# JBCBJ.net
KiCad netlist of a schematic drawn in Altium Designer
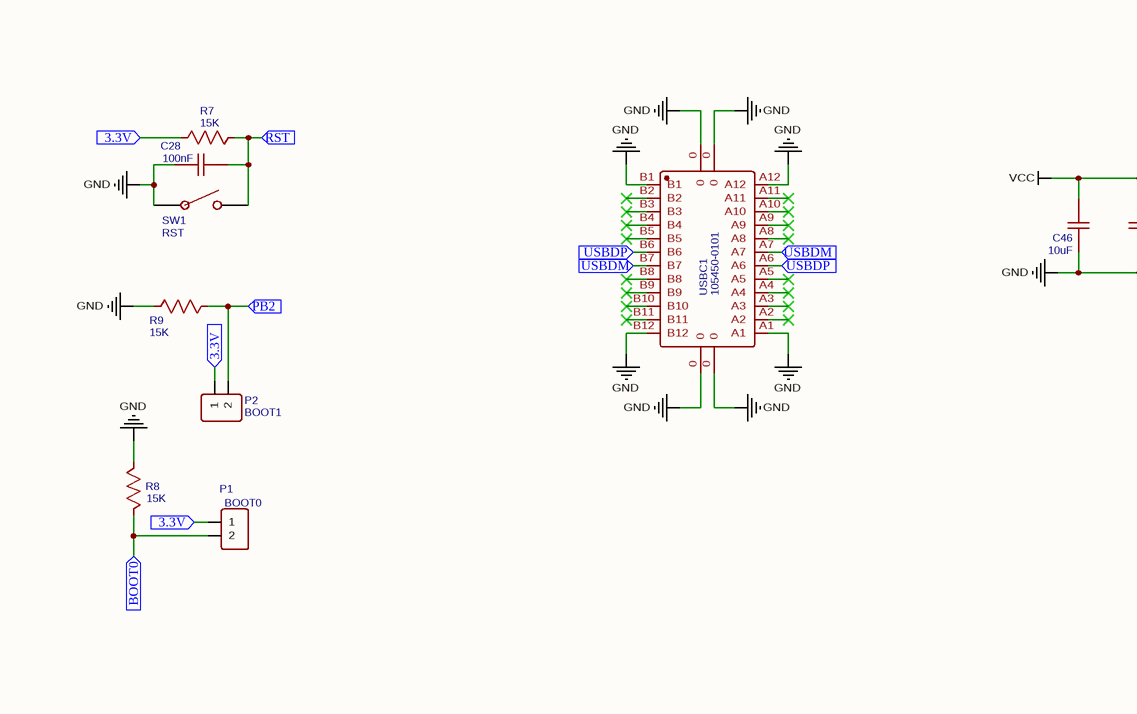
[diagram p0: JBCBJ.schdoc, top left]
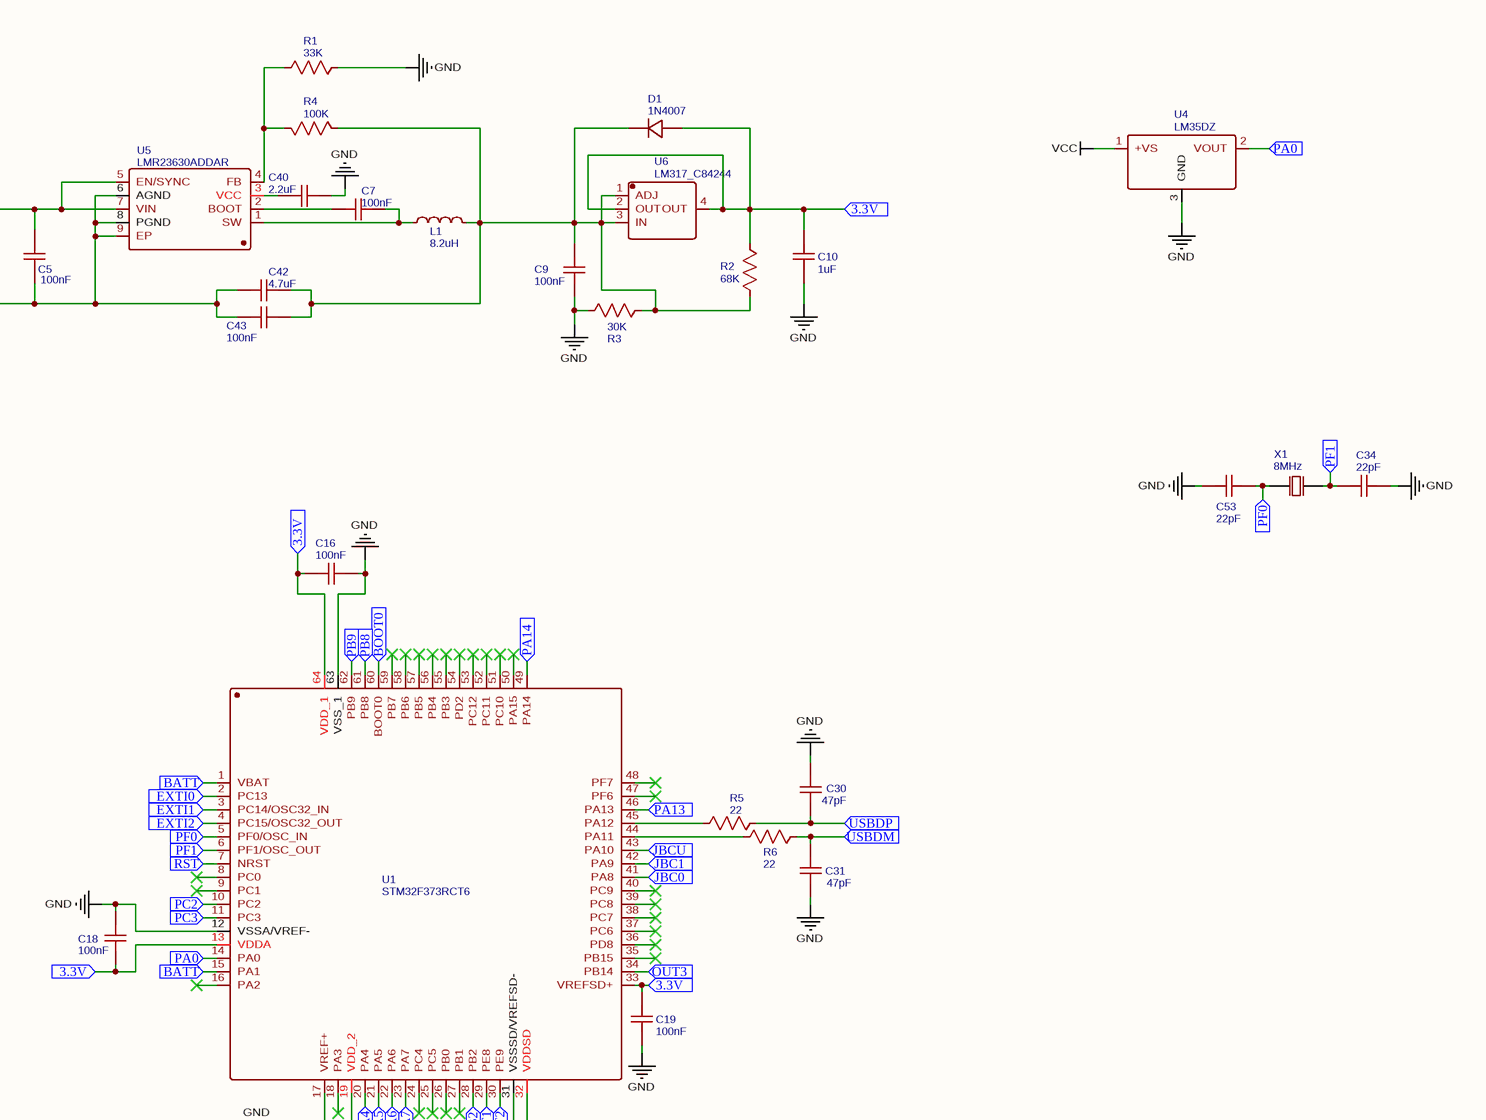
[diagram p1: JBCBJ.schdoc, top right]
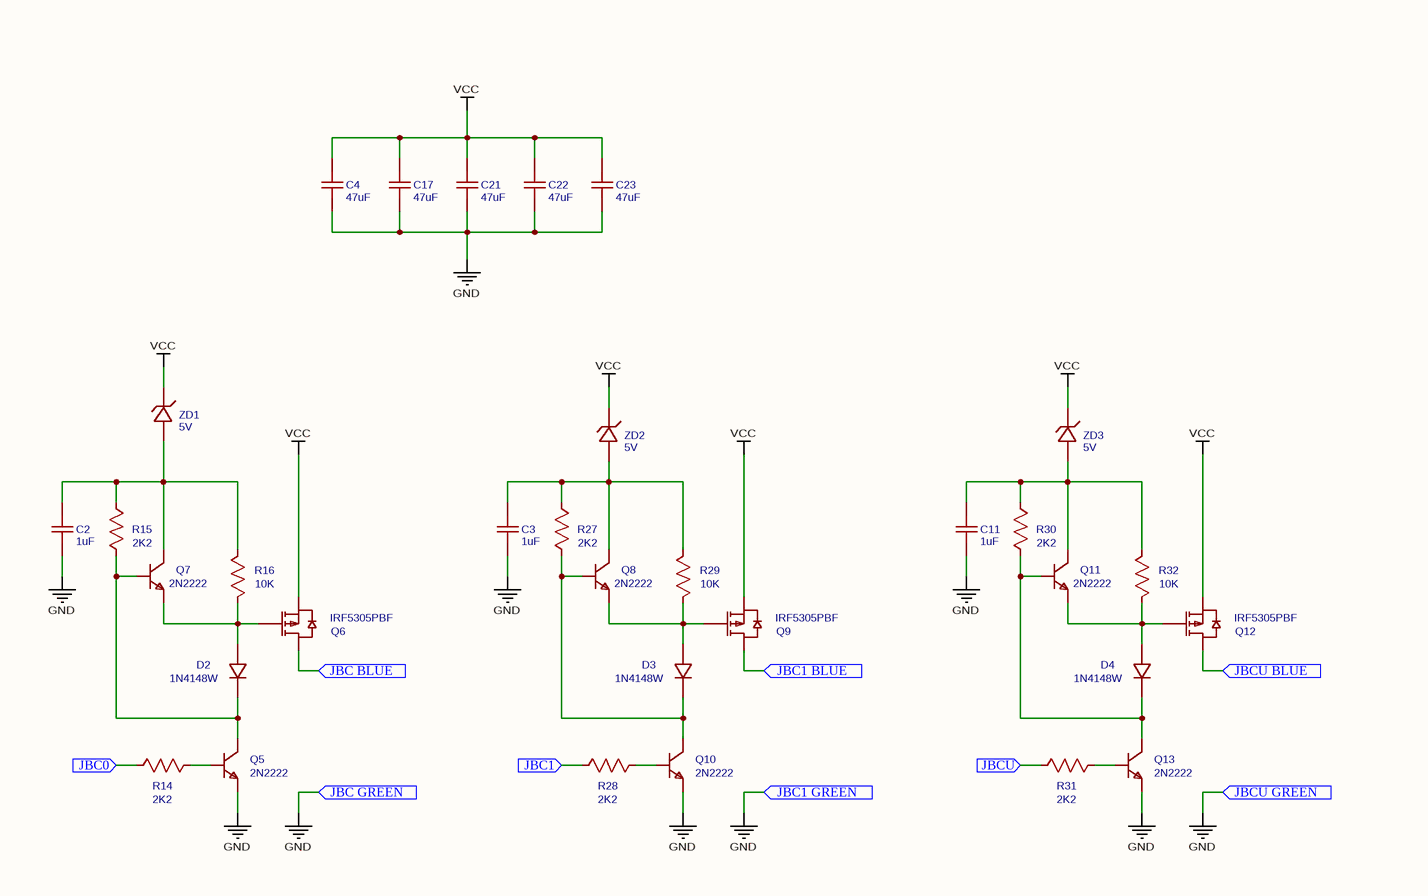
[diagram p2: JBCBJ.schdoc, bottom left]
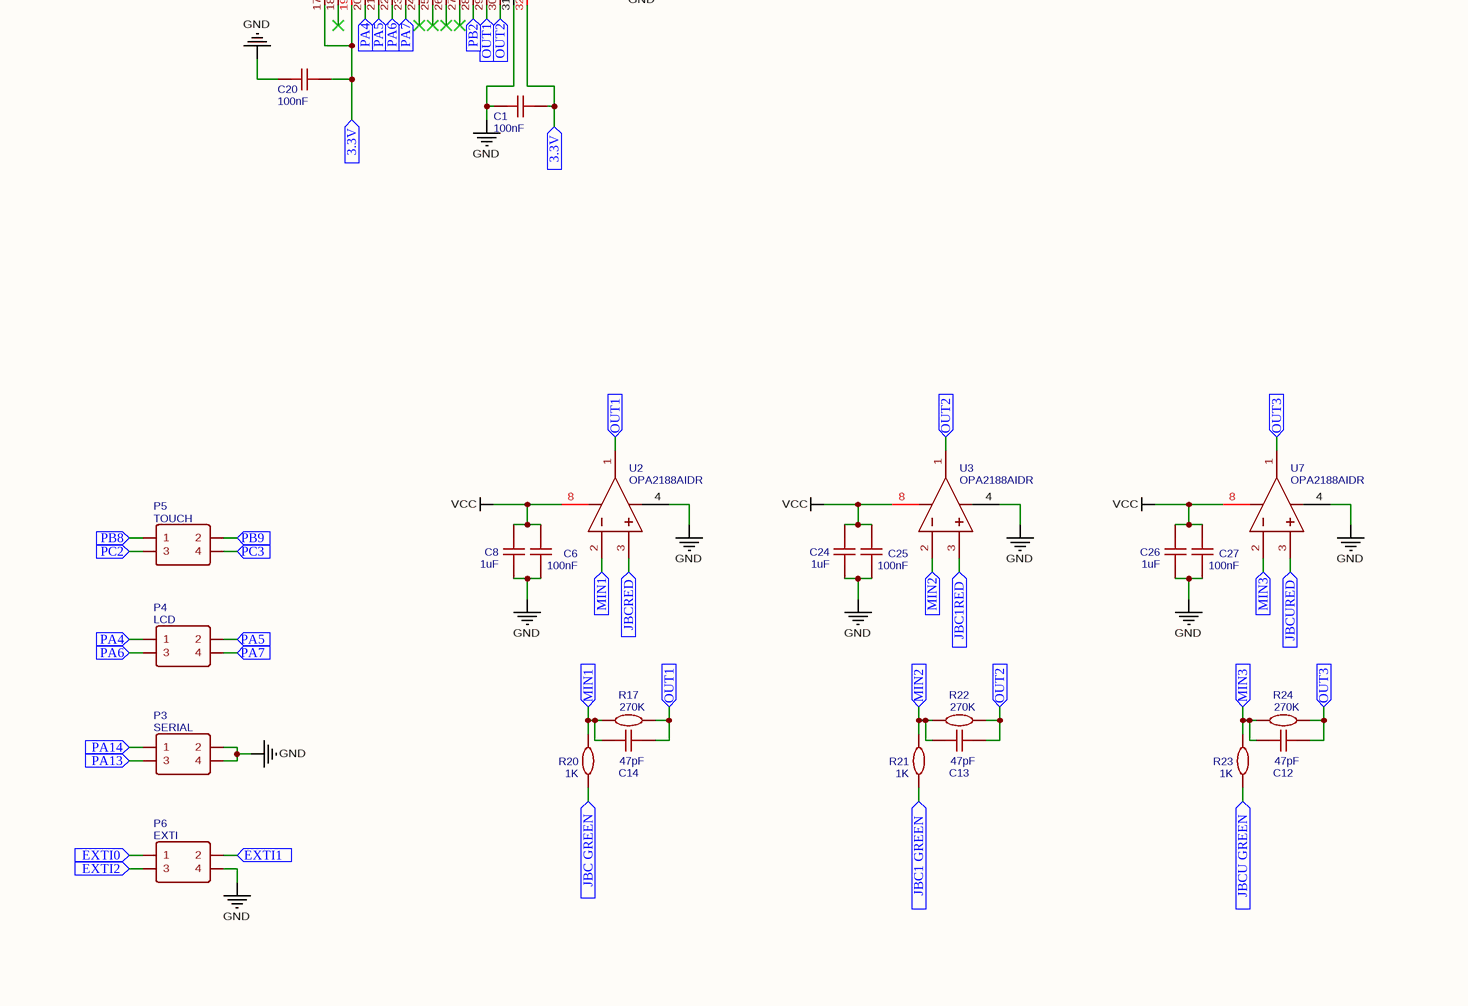
[diagram p3: JBCBJ.schdoc, bottom right]

(export (version "E")
  (design (tool "Eeschema 10.0.6"))
  (components
    (comp (ref "C1")
      (value "100nF")
      (footprint "C0603")
      (libsource (lib "altium-import") (part "root_1_100nF_"))
    )
    (comp (ref "C2")
      (value "1uF")
      (footprint "C0603")
      (fields (field (name "CONTRIBUTOR") "LCEDA_Lib"))
      (libsource (lib "altium-import") (part "root_1_1uF_"))
    )
    (comp (ref "C3")
      (value "1uF")
      (footprint "C0603")
      (fields (field (name "CONTRIBUTOR") "LCEDA_Lib"))
      (libsource (lib "altium-import") (part "root_1_1uF_"))
    )
    (comp (ref "C4")
      (value "47uF")
      (footprint "C1206")
      (fields (field (name "CONTRIBUTOR") "LCEDA_Lib"))
      (libsource (lib "altium-import") (part "root_1_47uF_"))
    )
    (comp (ref "C5") (value "100nF") (footprint "C0603") (libsource (lib "") (part "root_2_100nF__1")))
    (comp (ref "C6")
      (value "100nF")
      (footprint "C0603")
      (libsource (lib "altium-import") (part "root_2_100nF_"))
    )
    (comp (ref "C7")
      (value "100nF")
      (footprint "C0603")
      (libsource (lib "altium-import") (part "root_1_100nF_"))
    )
    (comp (ref "C8") (value "1uF") (footprint "C0603") (libsource (lib "altium-import") (part "root_2_1uF_")))
    (comp (ref "C9")
      (value "100nF")
      (footprint "C0603")
      (libsource (lib "altium-import") (part "root_0_100nF_"))
    )
    (comp (ref "C10")
      (value "1uF")
      (footprint "C0603")
      (libsource (lib "altium-import") (part "root_0_1uF_"))
    )
    (comp (ref "C11")
      (value "1uF")
      (footprint "C0603")
      (fields (field (name "CONTRIBUTOR") "LCEDA_Lib"))
      (libsource (lib "altium-import") (part "root_1_1uF_"))
    )
    (comp (ref "C12")
      (value "47pF")
      (footprint "C0603")
      (libsource (lib "altium-import") (part "root_3_47pF_"))
    )
    (comp (ref "C13")
      (value "47pF")
      (footprint "C0603")
      (libsource (lib "altium-import") (part "root_3_47pF_"))
    )
    (comp (ref "C14")
      (value "47pF")
      (footprint "C0603")
      (libsource (lib "altium-import") (part "root_3_47pF_"))
    )
    (comp (ref "C16")
      (value "100nF")
      (footprint "C0603")
      (libsource (lib "altium-import") (part "root_3_100nF_"))
    )
    (comp (ref "C17")
      (value "47uF")
      (footprint "C1206")
      (fields (field (name "CONTRIBUTOR") "LCEDA_Lib"))
      (libsource (lib "altium-import") (part "root_1_47uF_"))
    )
    (comp (ref "C18")
      (value "100nF")
      (footprint "C0603")
      (libsource (lib "altium-import") (part "root_0_100nF_"))
    )
    (comp (ref "C19")
      (value "100nF")
      (footprint "C0603")
      (libsource (lib "altium-import") (part "root_2_100nF_"))
    )
    (comp (ref "C20")
      (value "100nF")
      (footprint "C0603")
      (libsource (lib "altium-import") (part "root_1_100nF_"))
    )
    (comp (ref "C21")
      (value "47uF")
      (footprint "C1206")
      (fields (field (name "CONTRIBUTOR") "LCEDA_Lib"))
      (libsource (lib "altium-import") (part "root_1_47uF_"))
    )
    (comp (ref "C22")
      (value "47uF")
      (footprint "C1206")
      (fields (field (name "CONTRIBUTOR") "LCEDA_Lib"))
      (libsource (lib "altium-import") (part "root_1_47uF_"))
    )
    (comp (ref "C23")
      (value "47uF")
      (footprint "C1206")
      (fields (field (name "CONTRIBUTOR") "LCEDA_Lib"))
      (libsource (lib "altium-import") (part "root_1_47uF_"))
    )
    (comp (ref "C24")
      (value "1uF")
      (footprint "C0603")
      (libsource (lib "altium-import") (part "root_2_1uF_"))
    )
    (comp (ref "C25")
      (value "100nF")
      (footprint "C0603")
      (libsource (lib "altium-import") (part "root_2_100nF_"))
    )
    (comp (ref "C26")
      (value "1uF")
      (footprint "C0603")
      (libsource (lib "altium-import") (part "root_2_1uF_"))
    )
    (comp (ref "C27")
      (value "100nF")
      (footprint "C0603")
      (libsource (lib "altium-import") (part "root_2_100nF_"))
    )
    (comp (ref "C28") (value "100nF") (footprint "C0603") (libsource (lib "") (part "root_1_100nF__1")))
    (comp (ref "C30")
      (value "47pF")
      (footprint "C0603")
      (libsource (lib "altium-import") (part "root_2_47pF_"))
    )
    (comp (ref "C31")
      (value "47pF")
      (footprint "C0603")
      (libsource (lib "altium-import") (part "root_0_47pF_"))
    )
    (comp (ref "C34")
      (value "22pF")
      (footprint "C0603")
      (libsource (lib "altium-import") (part "root_3_22pF_"))
    )
    (comp (ref "C40")
      (value "2.2uF")
      (footprint "C0603")
      (libsource (lib "altium-import") (part "root_1_2.2uF_"))
    )
    (comp (ref "C42")
      (value "4.7uF")
      (footprint "C0603")
      (libsource (lib "altium-import") (part "root_1_4.7uF_"))
    )
    (comp (ref "C43")
      (value "100nF")
      (footprint "C0603")
      (libsource (lib "altium-import") (part "root_1_100nF_"))
    )
    (comp (ref "C46")
      (value "10uF")
      (footprint "C0603")
      (libsource (lib "altium-import") (part "root_2_10uF_"))
    )
    (comp (ref "C53")
      (value "22pF")
      (footprint "C0603")
      (libsource (lib "altium-import") (part "root_3_22pF_"))
    )
    (comp (ref "D1")
      (value "1N4007")
      (footprint "DO-214BA_L4.8-W2.9-LS5.3-RD")
      (fields (field (name "BOM_SUPPLIER PART") "C106903"))
      (libsource (lib "altium-import") (part "root_0_1N4007_"))
    )
    (comp (ref "D2")
      (value "1N4148W")
      (footprint "SOD-323F_L2.0-W1.6-LS2.5-RD")
      (fields (field (name "BOM_SUPPLIER PART") "C129216") (field (name "CONTRIBUTOR") "LCEDA_Lib"))
      (libsource (lib "altium-import") (part "root_3_1N4148W_"))
    )
    (comp (ref "D3")
      (value "1N4148W")
      (footprint "SOD-323F_L2.0-W1.6-LS2.5-RD")
      (fields (field (name "BOM_SUPPLIER PART") "C129216") (field (name "CONTRIBUTOR") "LCEDA_Lib"))
      (libsource (lib "altium-import") (part "root_3_1N4148W_"))
    )
    (comp (ref "D4")
      (value "1N4148W")
      (footprint "SOD-323F_L2.0-W1.6-LS2.5-RD")
      (fields (field (name "BOM_SUPPLIER PART") "C129216") (field (name "CONTRIBUTOR") "LCEDA_Lib"))
      (libsource (lib "altium-import") (part "root_3_1N4148W_"))
    )
    (comp (ref "L1")
      (value "8.2uH")
      (footprint "IND-SMD_L7.8-W7.0_MAPM0630F")
      (fields
        (field (name "BOM_SUPPLIER PART") "C280926")
        (field (name "BOM_MANUFACTURER PART") "MAPM0630F-8R2M-LF")
        (field (name "CONTRIBUTOR") "LCSC")
      )
      (libsource (lib "altium-import") (part "root_2_8.2uH_"))
    )
    (comp (ref "P1")
      (value "BOOT0")
      (footprint "HDR-TH_2P-P2.54-V-M")
      (fields
        (field (name "BOM_MANUFACTURER PART") "2.54-1*2PFemale")
        (field (name "BOM_SUPPLIER PART") "C49661")
      )
      (libsource (lib "altium-import") (part "root_0_BOOT0_"))
    )
    (comp (ref "P2")
      (value "BOOT1")
      (footprint "HDR-TH_2P-P2.54-V-M")
      (fields
        (field (name "BOM_MANUFACTURER PART") "2.54-1*2PFemale")
        (field (name "BOM_SUPPLIER PART") "C49661")
      )
      (libsource (lib "altium-import") (part "root_3_BOOT1_"))
    )
    (comp (ref "P3")
      (value "SERIAL")
      (footprint "HDR-TH_4PIN-V-ROW2-COL2-MALE-PITCH2.54")
      (fields
        (field (name "BOM_MANUFACTURER PART") "Double Rows2.54mm2*2pHeaders  Pins")
        (field (name "BOM_SUPPLIER PART") "C66690")
      )
      (libsource (lib "altium-import") (part "root_0_SERIAL_"))
    )
    (comp (ref "P4")
      (value "LCD")
      (footprint "HDR-TH_4PIN-V-ROW2-COL2-MALE-PITCH2.54")
      (fields
        (field (name "BOM_MANUFACTURER PART") "Double Rows2.54mm2*2pHeaders  Pins")
        (field (name "BOM_SUPPLIER PART") "C66690")
      )
      (libsource (lib "altium-import") (part "root_0_LCD_"))
    )
    (comp (ref "P5")
      (value "TOUCH")
      (footprint "HDR-TH_4PIN-V-ROW2-COL2-MALE-PITCH2.54")
      (fields
        (field (name "BOM_MANUFACTURER PART") "Double Rows2.54mm2*2pHeaders  Pins")
        (field (name "BOM_SUPPLIER PART") "C66690")
      )
      (libsource (lib "altium-import") (part "root_0_TOUCH_"))
    )
    (comp (ref "P6")
      (value "EXTI")
      (footprint "HDR-TH_4PIN-V-ROW2-COL2-MALE-PITCH2.54")
      (fields
        (field (name "BOM_MANUFACTURER PART") "Double Rows2.54mm2*2pHeaders  Pins")
        (field (name "BOM_SUPPLIER PART") "C66690")
      )
      (libsource (lib "altium-import") (part "root_0_EXTI_"))
    )
    (comp (ref "Q5")
      (value "2N2222")
      (footprint "SOT-23-3_L2.9-W1.3-P1.90-LS2.4-BR")
      (fields (field (name "BOM_MANUFACTURER PART") "2N3904") (field (name "BOM_SUPPLIER PART") "C118538"))
      (libsource (lib "altium-import") (part "root_0_2N2222_"))
    )
    (comp (ref "Q6")
      (value "IRF5305PBF")
      (footprint "DPAK-3_L6.6-W6.1-P2.28-LS9.9-BR")
      (fields (field (name "BOM_SUPPLIER PART") "C2623"))
      (libsource (lib "altium-import") (part "root_0_IRF5305PBF_"))
    )
    (comp (ref "Q7")
      (value "2N2222")
      (footprint "SOT-23-3_L2.9-W1.3-P1.90-LS2.4-BR")
      (fields (field (name "BOM_SUPPLIER PART") "C118536") (field (name "CONTRIBUTOR") "LCSC"))
      (libsource (lib "altium-import") (part "root_0_2N2222_"))
    )
    (comp (ref "Q8")
      (value "2N2222")
      (footprint "SOT-23-3_L2.9-W1.3-P1.90-LS2.4-BR")
      (fields (field (name "BOM_SUPPLIER PART") "C118536") (field (name "CONTRIBUTOR") "LCSC"))
      (libsource (lib "altium-import") (part "root_0_2N2222_"))
    )
    (comp (ref "Q9")
      (value "IRF5305PBF")
      (footprint "DPAK-3_L6.6-W6.1-P2.28-LS9.9-BR")
      (fields (field (name "BOM_SUPPLIER PART") "C2623"))
      (libsource (lib "altium-import") (part "root_0_IRF5305PBF_"))
    )
    (comp (ref "Q10")
      (value "2N2222")
      (footprint "SOT-23-3_L2.9-W1.3-P1.90-LS2.4-BR")
      (fields (field (name "BOM_MANUFACTURER PART") "2N3904") (field (name "BOM_SUPPLIER PART") "C118538"))
      (libsource (lib "altium-import") (part "root_0_2N2222_"))
    )
    (comp (ref "Q11")
      (value "2N2222")
      (footprint "SOT-23-3_L2.9-W1.3-P1.90-LS2.4-BR")
      (fields (field (name "BOM_SUPPLIER PART") "C118536") (field (name "CONTRIBUTOR") "LCSC"))
      (libsource (lib "altium-import") (part "root_0_2N2222_"))
    )
    (comp (ref "Q12")
      (value "IRF5305PBF")
      (footprint "DPAK-3_L6.6-W6.1-P2.28-LS9.9-BR")
      (fields (field (name "BOM_SUPPLIER PART") "C2623"))
      (libsource (lib "altium-import") (part "root_0_IRF5305PBF_"))
    )
    (comp (ref "Q13")
      (value "2N2222")
      (footprint "SOT-23-3_L2.9-W1.3-P1.90-LS2.4-BR")
      (fields (field (name "BOM_MANUFACTURER PART") "2N3904") (field (name "BOM_SUPPLIER PART") "C118538"))
      (libsource (lib "altium-import") (part "root_0_2N2222_"))
    )
    (comp (ref "R1") (value "33K") (footprint "R0603") (libsource (lib "altium-import") (part "root_2_33K_")))
    (comp (ref "R2") (value "68K") (footprint "R0603") (libsource (lib "altium-import") (part "root_1_68K_")))
    (comp (ref "R3") (value "30K") (footprint "R0603") (libsource (lib "altium-import") (part "root_2_30K_")))
    (comp (ref "R4")
      (value "100K")
      (footprint "R0603")
      (libsource (lib "altium-import") (part "root_0_100K_"))
    )
    (comp (ref "R5") (value "22") (footprint "R0603") (libsource (lib "altium-import") (part "root_0_22_")))
    (comp (ref "R6") (value "22") (footprint "R0603") (libsource (lib "altium-import") (part "root_0_22_")))
    (comp (ref "R7") (value "15K") (footprint "R0603") (libsource (lib "altium-import") (part "root_0_15K_")))
    (comp (ref "R8") (value "15K") (footprint "R0603") (libsource (lib "altium-import") (part "root_3_15K_")))
    (comp (ref "R9") (value "15K") (footprint "R0603") (libsource (lib "altium-import") (part "root_2_15K_")))
    (comp (ref "R14")
      (value "2K2")
      (footprint "R0603")
      (fields (field (name "CONTRIBUTOR") "LCEDA_Lib"))
      (libsource (lib "altium-import") (part "root_0_2K2_"))
    )
    (comp (ref "R15")
      (value "2K2")
      (footprint "R0603")
      (fields (field (name "CONTRIBUTOR") "LCEDA_Lib"))
      (libsource (lib "altium-import") (part "root_1_2K2_"))
    )
    (comp (ref "R16")
      (value "10K")
      (footprint "R0603")
      (libsource (lib "altium-import") (part "root_3_10K_"))
    )
    (comp (ref "R17")
      (value "270K")
      (footprint "R0603")
      (fields
        (field (name "BOM_SUPPLIER PART") "C351588")
        (field (name "BOM_MANUFACTURER PART") "PTFR0805B270KN9")
        (field (name "CONTRIBUTOR") "LCSC")
      )
      (libsource (lib "altium-import") (part "root_2_270K_"))
    )
    (comp (ref "R20")
      (value "1K")
      (footprint "R0603")
      (fields
        (field (name "BOM_SUPPLIER PART") "C192073")
        (field (name "BOM_MANUFACTURER PART") "ERA-6AEB102V")
        (field (name "CONTRIBUTOR") "LCSC")
      )
      (libsource (lib "altium-import") (part "root_1_1K_"))
    )
    (comp (ref "R21")
      (value "1K")
      (footprint "R0603")
      (fields
        (field (name "BOM_SUPPLIER PART") "C192073")
        (field (name "BOM_MANUFACTURER PART") "ERA-6AEB102V")
        (field (name "CONTRIBUTOR") "LCSC")
      )
      (libsource (lib "altium-import") (part "root_1_1K_"))
    )
    (comp (ref "R22")
      (value "270K")
      (footprint "R0603")
      (fields
        (field (name "BOM_SUPPLIER PART") "C351588")
        (field (name "BOM_MANUFACTURER PART") "PTFR0805B270KN9")
        (field (name "CONTRIBUTOR") "LCSC")
      )
      (libsource (lib "altium-import") (part "root_2_270K_"))
    )
    (comp (ref "R23")
      (value "1K")
      (footprint "R0603")
      (fields
        (field (name "BOM_SUPPLIER PART") "C192073")
        (field (name "BOM_MANUFACTURER PART") "ERA-6AEB102V")
        (field (name "CONTRIBUTOR") "LCSC")
      )
      (libsource (lib "altium-import") (part "root_1_1K_"))
    )
    (comp (ref "R24")
      (value "270K")
      (footprint "R0603")
      (fields
        (field (name "BOM_SUPPLIER PART") "C351588")
        (field (name "BOM_MANUFACTURER PART") "PTFR0805B270KN9")
        (field (name "CONTRIBUTOR") "LCSC")
      )
      (libsource (lib "altium-import") (part "root_2_270K_"))
    )
    (comp (ref "R27")
      (value "2K2")
      (footprint "R0603")
      (fields (field (name "CONTRIBUTOR") "LCEDA_Lib"))
      (libsource (lib "altium-import") (part "root_1_2K2_"))
    )
    (comp (ref "R28")
      (value "2K2")
      (footprint "R0603")
      (fields (field (name "CONTRIBUTOR") "LCEDA_Lib"))
      (libsource (lib "altium-import") (part "root_0_2K2_"))
    )
    (comp (ref "R29")
      (value "10K")
      (footprint "R0603")
      (libsource (lib "altium-import") (part "root_3_10K_"))
    )
    (comp (ref "R30")
      (value "2K2")
      (footprint "R0603")
      (fields (field (name "CONTRIBUTOR") "LCEDA_Lib"))
      (libsource (lib "altium-import") (part "root_1_2K2_"))
    )
    (comp (ref "R31")
      (value "2K2")
      (footprint "R0603")
      (fields (field (name "CONTRIBUTOR") "LCEDA_Lib"))
      (libsource (lib "altium-import") (part "root_0_2K2_"))
    )
    (comp (ref "R32")
      (value "10K")
      (footprint "R0603")
      (libsource (lib "altium-import") (part "root_3_10K_"))
    )
    (comp (ref "SW1")
      (value "RST")
      (footprint "KEY-6.0*6.0-4")
      (fields
        (field (name "BOM_MANUFACTURER PART") "EVQ22705R")
        (field (name "BOM_SUPPLIER PART") "C79156")
        (field (name "CONTRIBUTOR") "LCSC")
      )
      (libsource (lib "altium-import") (part "root_0_RST_"))
    )
    (comp (ref "U1")
      (value "STM32F373RCT6")
      (footprint "LQFP-64_L10.0-W10.0-P0.50-LS12.0-TL")
      (fields (field (name "BOM_SUPPLIER PART") "C84174"))
      (libsource (lib "altium-import") (part "root_0_STM32F373RCT6_"))
    )
    (comp (ref "U2")
      (value "OPA2188AIDR")
      (footprint "SOIC-8_L4.9-W3.9-P1.27-LS6.0-BL")
      (fields (field (name "BOM_SUPPLIER PART") "C17271") (field (name "SUBPART_NO") "1"))
      (libsource (lib "altium-import") (part "root_1_OPA2188AIDR_"))
    )
    (comp (ref "U3")
      (value "OPA2188AIDR")
      (footprint "SOIC-8_L4.9-W3.9-P1.27-LS6.0-BL")
      (fields (field (name "BOM_SUPPLIER PART") "C17271") (field (name "SUBPART_NO") "1"))
      (libsource (lib "altium-import") (part "root_1_OPA2188AIDR_"))
    )
    (comp (ref "U4")
      (value "LM35DZ")
      (footprint "TO-92-3_L4.9-W3.7-P1.27-L")
      (fields (field (name "BOM_SUPPLIER PART") "C12165"))
      (libsource (lib "altium-import") (part "root_0_LM35DZ_"))
    )
    (comp (ref "U5")
      (value "LMR23630ADDAR")
      (footprint "SO-8_L4.9-W3.9-P1.27-LS6.0-BL-EP")
      (fields (field (name "BOM_SUPPLIER PART") "C477923") (field (name "CONTRIBUTOR") "LCSC"))
      (libsource (lib "altium-import") (part "root_2_LMR23630ADDAR_"))
    )
    (comp (ref "U6")
      (value "LM317_C84244")
      (footprint "SOT-223-3_L6.5-W3.4-P2.30-LS7.0-BR")
      (fields (field (name "BOM_MANUFACTURER PART") "LM317") (field (name "BOM_SUPPLIER PART") "C84244"))
      (libsource (lib "altium-import") (part "root_0_LM317_C84244_"))
    )
    (comp (ref "U7")
      (value "OPA2188AIDR")
      (footprint "SOIC-8_L4.9-W3.9-P1.27-LS6.0-BL")
      (fields (field (name "BOM_SUPPLIER PART") "C17271") (field (name "SUBPART_NO") "1"))
      (libsource (lib "altium-import") (part "root_1_OPA2188AIDR_"))
    )
    (comp (ref "USBC1")
      (value "105450-0101")
      (footprint "USB-C-SMD_TYPE-C-USB-18")
      (fields (field (name "BOM_SUPPLIER PART") "C134092") (field (name "CONTRIBUTOR") "LCSC"))
      (libsource (lib "altium-import") (part "root_0_105450-0101_"))
    )
    (comp (ref "X1")
      (value "8MHz")
      (footprint "HC-49US_L11.5-W4.5-P4.88")
      (fields
        (field (name "BOM_SUPPLIER PART") "C188205")
        (field (name "BOM_MANUFACTURER PART") "X49SD8MSB2SI")
        (field (name "CONTRIBUTOR") "LCSC")
      )
      (libsource (lib "altium-import") (part "root_0_8MHz_"))
    )
    (comp (ref "ZD1")
      (value "5V")
      (footprint "VERTICAL DO41 DIODE")
      (fields (field (name "BOM_MANUFACTURER PART") "BZX84C5V1") (field (name "BOM_SUPPLIER PART") "C27131"))
      (libsource (lib "altium-import") (part "root_1_5V_"))
    )
    (comp (ref "ZD2")
      (value "5V")
      (footprint "VERTICAL DO41 DIODE")
      (fields (field (name "BOM_MANUFACTURER PART") "BZX84C5V1") (field (name "BOM_SUPPLIER PART") "C27131"))
      (libsource (lib "altium-import") (part "root_1_5V_"))
    )
    (comp (ref "ZD3")
      (value "5V")
      (footprint "VERTICAL DO41 DIODE")
      (fields (field (name "BOM_MANUFACTURER PART") "BZX84C5V1") (field (name "BOM_SUPPLIER PART") "C27131"))
      (libsource (lib "altium-import") (part "root_1_5V_"))
    )
  )
  (nets
    (net (code "1") (name "/3.3V") (class "Default")
      (node (ref "C1") (pin "1") (pinfunction "1_1") (pintype "passive"))
      (node (ref "C10") (pin "2") (pinfunction "2_2") (pintype "passive"))
      (node (ref "C16") (pin "1") (pinfunction "1_1") (pintype "passive"))
      (node (ref "C18") (pin "1") (pinfunction "1_1") (pintype "passive"))
      (node (ref "C19") (pin "1") (pinfunction "1_1") (pintype "passive"))
      (node (ref "C20") (pin "1") (pinfunction "1_1") (pintype "passive"))
      (node (ref "D1") (pin "2") (pinfunction "A_2") (pintype "passive"))
      (node (ref "P1") (pin "1") (pinfunction "1_1") (pintype "passive"))
      (node (ref "P2") (pin "1") (pinfunction "1_1") (pintype "passive"))
      (node (ref "R2") (pin "2") (pinfunction "2_2") (pintype "passive"))
      (node (ref "R7") (pin "1") (pinfunction "1_1") (pintype "passive"))
      (node (ref "U1") (pin "13") (pinfunction "VDDA_13") (pintype "passive"))
      (node (ref "U1") (pin "17") (pinfunction "VREF+_17") (pintype "passive"))
      (node (ref "U1") (pin "19") (pinfunction "VDD_2_19") (pintype "passive"))
      (node (ref "U1") (pin "32") (pinfunction "VDDSD_32") (pintype "passive"))
      (node (ref "U1") (pin "33") (pinfunction "VREFSD+_33") (pintype "passive"))
      (node (ref "U1") (pin "64") (pinfunction "VDD_1_64") (pintype "passive"))
      (node (ref "U6") (pin "2") (pinfunction "OUT_2") (pintype "passive"))
      (node (ref "U6") (pin "4") (pinfunction "OUT_4") (pintype "passive"))
    )
    (net (code "2") (name "/BATT") (class "Default")
      (node (ref "U1") (pin "1") (pinfunction "VBAT_1") (pintype "passive"))
      (node (ref "U1") (pin "15") (pinfunction "PA1_15") (pintype "passive"))
    )
    (net (code "3") (name "/BOOT0") (class "Default")
      (node (ref "P1") (pin "2") (pinfunction "2_2") (pintype "passive"))
      (node (ref "R8") (pin "1") (pinfunction "1_1") (pintype "passive"))
      (node (ref "U1") (pin "60") (pinfunction "BOOT0_60") (pintype "passive"))
    )
    (net (code "4") (name "/EXTI0") (class "Default")
      (node (ref "P6") (pin "1") (pinfunction "1_1") (pintype "passive"))
      (node (ref "U1") (pin "2") (pinfunction "PC13_2") (pintype "passive"))
    )
    (net (code "5") (name "/EXTI1") (class "Default")
      (node (ref "P6") (pin "2") (pinfunction "2_2") (pintype "passive"))
      (node (ref "U1") (pin "3") (pinfunction "PC14/OSC32_IN_3") (pintype "passive"))
    )
    (net (code "6") (name "/EXTI2") (class "Default")
      (node (ref "P6") (pin "3") (pinfunction "3_3") (pintype "passive"))
      (node (ref "U1") (pin "4") (pinfunction "PC15/OSC32_OUT_4") (pintype "passive"))
    )
    (net (code "7") (name "/JBC BLUE") (class "Default")
      (node (ref "Q6") (pin "2") (pinfunction "D_2") (pintype "passive"))
    )
    (net (code "8") (name "/JBC0") (class "Default")
      (node (ref "R14") (pin "1") (pinfunction "1_1") (pintype "passive"))
      (node (ref "U1") (pin "41") (pinfunction "PA8_41") (pintype "passive"))
    )
    (net (code "9") (name "/JBC1") (class "Default")
      (node (ref "R28") (pin "1") (pinfunction "1_1") (pintype "passive"))
      (node (ref "U1") (pin "42") (pinfunction "PA9_42") (pintype "passive"))
    )
    (net (code "10") (name "/JBC1 BLUE") (class "Default")
      (node (ref "Q9") (pin "2") (pinfunction "D_2") (pintype "passive"))
    )
    (net (code "11") (name "/JBC1RED") (class "Default")
      (node (ref "U3") (pin "3") (pinfunction "IN_A+_3") (pintype "passive"))
    )
    (net (code "12") (name "/JBCRED") (class "Default")
      (node (ref "U2") (pin "3") (pinfunction "IN_A+_3") (pintype "passive"))
    )
    (net (code "13") (name "/JBCU") (class "Default")
      (node (ref "R31") (pin "1") (pinfunction "1_1") (pintype "passive"))
      (node (ref "U1") (pin "43") (pinfunction "PA10_43") (pintype "passive"))
    )
    (net (code "14") (name "/JBCU BLUE") (class "Default")
      (node (ref "Q12") (pin "2") (pinfunction "D_2") (pintype "passive"))
    )
    (net (code "15") (name "/JBCURED") (class "Default")
      (node (ref "U7") (pin "3") (pinfunction "IN_A+_3") (pintype "passive"))
    )
    (net (code "16") (name "/MIN1") (class "Default")
      (node (ref "C14") (pin "1") (pinfunction "1_1") (pintype "passive"))
      (node (ref "R17") (pin "2") (pinfunction "2_2") (pintype "passive"))
      (node (ref "R20") (pin "2") (pinfunction "2_2") (pintype "passive"))
      (node (ref "U2") (pin "2") (pinfunction "IN_A-_2") (pintype "passive"))
    )
    (net (code "17") (name "/MIN2") (class "Default")
      (node (ref "C13") (pin "1") (pinfunction "1_1") (pintype "passive"))
      (node (ref "R21") (pin "2") (pinfunction "2_2") (pintype "passive"))
      (node (ref "R22") (pin "2") (pinfunction "2_2") (pintype "passive"))
      (node (ref "U3") (pin "2") (pinfunction "IN_A-_2") (pintype "passive"))
    )
    (net (code "18") (name "/MIN3") (class "Default")
      (node (ref "C12") (pin "1") (pinfunction "1_1") (pintype "passive"))
      (node (ref "R23") (pin "2") (pinfunction "2_2") (pintype "passive"))
      (node (ref "R24") (pin "2") (pinfunction "2_2") (pintype "passive"))
      (node (ref "U7") (pin "2") (pinfunction "IN_A-_2") (pintype "passive"))
    )
    (net (code "19") (name "/OUT1") (class "Default")
      (node (ref "C14") (pin "2") (pinfunction "2_2") (pintype "passive"))
      (node (ref "R17") (pin "1") (pinfunction "1_1") (pintype "passive"))
      (node (ref "U1") (pin "29") (pinfunction "PE8_29") (pintype "passive"))
      (node (ref "U2") (pin "1") (pinfunction "OUT_A_1") (pintype "passive"))
    )
    (net (code "20") (name "/OUT2") (class "Default")
      (node (ref "C13") (pin "2") (pinfunction "2_2") (pintype "passive"))
      (node (ref "R22") (pin "1") (pinfunction "1_1") (pintype "passive"))
      (node (ref "U1") (pin "30") (pinfunction "PE9_30") (pintype "passive"))
      (node (ref "U3") (pin "1") (pinfunction "OUT_A_1") (pintype "passive"))
    )
    (net (code "21") (name "/OUT3") (class "Default")
      (node (ref "C12") (pin "2") (pinfunction "2_2") (pintype "passive"))
      (node (ref "R24") (pin "1") (pinfunction "1_1") (pintype "passive"))
      (node (ref "U1") (pin "34") (pinfunction "PB14_34") (pintype "passive"))
      (node (ref "U7") (pin "1") (pinfunction "OUT_A_1") (pintype "passive"))
    )
    (net (code "22") (name "/PA0") (class "Default")
      (node (ref "U1") (pin "14") (pinfunction "PA0_14") (pintype "passive"))
      (node (ref "U4") (pin "2") (pinfunction "VOUT_2") (pintype "passive"))
    )
    (net (code "23") (name "/PA4") (class "Default")
      (node (ref "P4") (pin "1") (pinfunction "1_1") (pintype "passive"))
      (node (ref "U1") (pin "20") (pinfunction "PA4_20") (pintype "passive"))
    )
    (net (code "24") (name "/PA5") (class "Default")
      (node (ref "P4") (pin "2") (pinfunction "2_2") (pintype "passive"))
      (node (ref "U1") (pin "21") (pinfunction "PA5_21") (pintype "passive"))
    )
    (net (code "25") (name "/PA6") (class "Default")
      (node (ref "P4") (pin "3") (pinfunction "3_3") (pintype "passive"))
      (node (ref "U1") (pin "22") (pinfunction "PA6_22") (pintype "passive"))
    )
    (net (code "26") (name "/PA7") (class "Default")
      (node (ref "P4") (pin "4") (pinfunction "4_4") (pintype "passive"))
      (node (ref "U1") (pin "23") (pinfunction "PA7_23") (pintype "passive"))
    )
    (net (code "27") (name "/PA13") (class "Default")
      (node (ref "P3") (pin "3") (pinfunction "3_3") (pintype "passive"))
      (node (ref "U1") (pin "46") (pinfunction "PA13_46") (pintype "passive"))
    )
    (net (code "28") (name "/PA14") (class "Default")
      (node (ref "P3") (pin "1") (pinfunction "1_1") (pintype "passive"))
      (node (ref "U1") (pin "49") (pinfunction "PA14_49") (pintype "passive"))
    )
    (net (code "29") (name "/PB2") (class "Default")
      (node (ref "P2") (pin "2") (pinfunction "2_2") (pintype "passive"))
      (node (ref "R9") (pin "1") (pinfunction "1_1") (pintype "passive"))
      (node (ref "U1") (pin "28") (pinfunction "PB2_28") (pintype "passive"))
    )
    (net (code "30") (name "/PB8") (class "Default")
      (node (ref "P5") (pin "1") (pinfunction "1_1") (pintype "passive"))
      (node (ref "U1") (pin "61") (pinfunction "PB8_61") (pintype "passive"))
    )
    (net (code "31") (name "/PB9") (class "Default")
      (node (ref "P5") (pin "2") (pinfunction "2_2") (pintype "passive"))
      (node (ref "U1") (pin "62") (pinfunction "PB9_62") (pintype "passive"))
    )
    (net (code "32") (name "/PC2") (class "Default")
      (node (ref "P5") (pin "3") (pinfunction "3_3") (pintype "passive"))
      (node (ref "U1") (pin "10") (pinfunction "PC2_10") (pintype "passive"))
    )
    (net (code "33") (name "/PC3") (class "Default")
      (node (ref "P5") (pin "4") (pinfunction "4_4") (pintype "passive"))
      (node (ref "U1") (pin "11") (pinfunction "PC3_11") (pintype "passive"))
    )
    (net (code "34") (name "/PF0") (class "Default")
      (node (ref "C53") (pin "2") (pinfunction "2_2") (pintype "passive"))
      (node (ref "U1") (pin "5") (pinfunction "PF0/OSC_IN_5") (pintype "passive"))
      (node (ref "X1") (pin "1") (pinfunction "OSC1_1") (pintype "passive"))
    )
    (net (code "35") (name "/PF1") (class "Default")
      (node (ref "C34") (pin "1") (pinfunction "1_1") (pintype "passive"))
      (node (ref "U1") (pin "6") (pinfunction "PF1/OSC_OUT_6") (pintype "passive"))
      (node (ref "X1") (pin "2") (pinfunction "OSC2_2") (pintype "passive"))
    )
    (net (code "36") (name "/RST") (class "Default")
      (node (ref "C28") (pin "2") (pinfunction "2_2") (pintype "passive"))
      (node (ref "R7") (pin "2") (pinfunction "2_2") (pintype "passive"))
      (node (ref "SW1") (pin "2") (pinfunction "2_2") (pintype "passive"))
      (node (ref "U1") (pin "7") (pinfunction "NRST_7") (pintype "passive"))
    )
    (net (code "37") (name "/USBDM") (class "Default")
      (node (ref "C31") (pin "2") (pinfunction "2_2") (pintype "passive"))
      (node (ref "R6") (pin "2") (pinfunction "2_2") (pintype "passive"))
      (node (ref "USBC1") (pin "A7") (pinfunction "A7_A7") (pintype "passive"))
      (node (ref "USBC1") (pin "B7") (pinfunction "B7_B7") (pintype "passive"))
    )
    (net (code "38") (name "/USBDP") (class "Default")
      (node (ref "C30") (pin "2") (pinfunction "2_2") (pintype "passive"))
      (node (ref "R5") (pin "2") (pinfunction "2_2") (pintype "passive"))
      (node (ref "USBC1") (pin "A6") (pinfunction "A6_A6") (pintype "passive"))
      (node (ref "USBC1") (pin "B6") (pinfunction "B6_B6") (pintype "passive"))
    )
    (net (code "39") (name "GND") (class "Default")
      (node (ref "C1") (pin "2") (pinfunction "2_2") (pintype "passive"))
      (node (ref "C10") (pin "1") (pinfunction "1_1") (pintype "passive"))
      (node (ref "C11") (pin "1") (pinfunction "1_1") (pintype "passive"))
      (node (ref "C16") (pin "2") (pinfunction "2_2") (pintype "passive"))
      (node (ref "C17") (pin "1") (pinfunction "1_1") (pintype "passive"))
      (node (ref "C18") (pin "2") (pinfunction "2_2") (pintype "passive"))
      (node (ref "C19") (pin "2") (pinfunction "2_2") (pintype "passive"))
      (node (ref "C2") (pin "1") (pinfunction "1_1") (pintype "passive"))
      (node (ref "C20") (pin "2") (pinfunction "2_2") (pintype "passive"))
      (node (ref "C21") (pin "1") (pinfunction "1_1") (pintype "passive"))
      (node (ref "C22") (pin "1") (pinfunction "1_1") (pintype "passive"))
      (node (ref "C23") (pin "1") (pinfunction "1_1") (pintype "passive"))
      (node (ref "C24") (pin "2") (pinfunction "2_2") (pintype "passive"))
      (node (ref "C25") (pin "2") (pinfunction "2_2") (pintype "passive"))
      (node (ref "C26") (pin "2") (pinfunction "2_2") (pintype "passive"))
      (node (ref "C27") (pin "2") (pinfunction "2_2") (pintype "passive"))
      (node (ref "C28") (pin "1") (pinfunction "1_1") (pintype "passive"))
      (node (ref "C3") (pin "1") (pinfunction "1_1") (pintype "passive"))
      (node (ref "C30") (pin "1") (pinfunction "1_1") (pintype "passive"))
      (node (ref "C31") (pin "1") (pinfunction "1_1") (pintype "passive"))
      (node (ref "C34") (pin "2") (pinfunction "2_2") (pintype "passive"))
      (node (ref "C4") (pin "1") (pinfunction "1_1") (pintype "passive"))
      (node (ref "C40") (pin "1") (pinfunction "1_1") (pintype "passive"))
      (node (ref "C42") (pin "2") (pinfunction "2_2") (pintype "passive"))
      (node (ref "C43") (pin "2") (pinfunction "2_2") (pintype "passive"))
      (node (ref "C46") (pin "2") (pinfunction "2_2") (pintype "passive"))
      (node (ref "C5") (pin "2") (pinfunction "2_2") (pintype "passive"))
      (node (ref "C53") (pin "1") (pinfunction "1_1") (pintype "passive"))
      (node (ref "C6") (pin "2") (pinfunction "2_2") (pintype "passive"))
      (node (ref "C8") (pin "2") (pinfunction "2_2") (pintype "passive"))
      (node (ref "C9") (pin "1") (pinfunction "1_1") (pintype "passive"))
      (node (ref "P3") (pin "2") (pinfunction "2_2") (pintype "passive"))
      (node (ref "P3") (pin "4") (pinfunction "4_4") (pintype "passive"))
      (node (ref "P6") (pin "4") (pinfunction "4_4") (pintype "passive"))
      (node (ref "Q10") (pin "2") (pinfunction "E_2") (pintype "passive"))
      (node (ref "Q13") (pin "2") (pinfunction "E_2") (pintype "passive"))
      (node (ref "Q5") (pin "2") (pinfunction "E_2") (pintype "passive"))
      (node (ref "R1") (pin "1") (pinfunction "1_1") (pintype "passive"))
      (node (ref "R20") (pin "1") (pinfunction "1_1") (pintype "passive"))
      (node (ref "R21") (pin "1") (pinfunction "1_1") (pintype "passive"))
      (node (ref "R23") (pin "1") (pinfunction "1_1") (pintype "passive"))
      (node (ref "R3") (pin "2") (pinfunction "2_2") (pintype "passive"))
      (node (ref "R8") (pin "2") (pinfunction "2_2") (pintype "passive"))
      (node (ref "R9") (pin "2") (pinfunction "2_2") (pintype "passive"))
      (node (ref "SW1") (pin "1") (pinfunction "1_1") (pintype "passive"))
      (node (ref "U1") (pin "12") (pinfunction "VSSA/VREF-_12") (pintype "passive"))
      (node (ref "U1") (pin "31") (pinfunction "VSSSD/VREFSD-_31") (pintype "passive"))
      (node (ref "U1") (pin "63") (pinfunction "VSS_1_63") (pintype "passive"))
      (node (ref "U2") (pin "4") (pinfunction "V-_4") (pintype "passive"))
      (node (ref "U3") (pin "4") (pinfunction "V-_4") (pintype "passive"))
      (node (ref "U4") (pin "3") (pinfunction "GND_3") (pintype "passive"))
      (node (ref "U5") (pin "6") (pinfunction "AGND_6") (pintype "passive"))
      (node (ref "U5") (pin "8") (pinfunction "PGND_8") (pintype "passive"))
      (node (ref "U5") (pin "9") (pinfunction "EP_9") (pintype "passive"))
      (node (ref "U7") (pin "4") (pinfunction "V-_4") (pintype "passive"))
      (node (ref "USBC1") (pin "0") (pinfunction "0_0") (pintype "passive"))
      (node (ref "USBC1") (pin "A1") (pinfunction "A1_A1") (pintype "passive"))
      (node (ref "USBC1") (pin "A12") (pinfunction "A12_A12") (pintype "passive"))
      (node (ref "USBC1") (pin "B1") (pinfunction "B1_B1") (pintype "passive"))
      (node (ref "USBC1") (pin "B12") (pinfunction "B12_B12") (pintype "passive"))
    )
    (net (code "40") (name "Net-(D1-K)") (class "Default")
      (node (ref "C42") (pin "1") (pinfunction "1_1") (pintype "passive"))
      (node (ref "C43") (pin "1") (pinfunction "1_1") (pintype "passive"))
      (node (ref "C9") (pin "2") (pinfunction "2_2") (pintype "passive"))
      (node (ref "D1") (pin "1") (pinfunction "K_1") (pintype "passive"))
      (node (ref "L1") (pin "1") (pinfunction "1_1") (pintype "passive"))
      (node (ref "R2") (pin "1") (pinfunction "1_1") (pintype "passive"))
      (node (ref "R3") (pin "1") (pinfunction "1_1") (pintype "passive"))
      (node (ref "R4") (pin "2") (pinfunction "2_2") (pintype "passive"))
      (node (ref "U6") (pin "1") (pinfunction "ADJ_1") (pintype "passive"))
      (node (ref "U6") (pin "3") (pinfunction "IN_3") (pintype "passive"))
    )
    (net (code "41") (name "Net-(Q5-B)") (class "Default")
      (node (ref "Q5") (pin "1") (pinfunction "B_1") (pintype "passive"))
      (node (ref "R14") (pin "2") (pinfunction "2_2") (pintype "passive"))
    )
    (net (code "42") (name "Net-(Q5-C)") (class "Default")
      (node (ref "D2") (pin "1") (pinfunction "1_1") (pintype "passive"))
      (node (ref "Q5") (pin "3") (pinfunction "C_3") (pintype "passive"))
      (node (ref "Q7") (pin "1") (pinfunction "B_1") (pintype "passive"))
      (node (ref "R15") (pin "1") (pinfunction "1_1") (pintype "passive"))
    )
    (net (code "43") (name "Net-(Q6-G)") (class "Default")
      (node (ref "D2") (pin "2") (pinfunction "2_2") (pintype "passive"))
      (node (ref "Q6") (pin "1") (pinfunction "G_1") (pintype "passive"))
      (node (ref "Q7") (pin "2") (pinfunction "E_2") (pintype "passive"))
      (node (ref "R16") (pin "2") (pinfunction "2_2") (pintype "passive"))
    )
    (net (code "44") (name "Net-(Q7-C)") (class "Default")
      (node (ref "C2") (pin "2") (pinfunction "2_2") (pintype "passive"))
      (node (ref "Q7") (pin "3") (pinfunction "C_3") (pintype "passive"))
      (node (ref "R15") (pin "2") (pinfunction "2_2") (pintype "passive"))
      (node (ref "R16") (pin "1") (pinfunction "1_1") (pintype "passive"))
      (node (ref "ZD1") (pin "1") (pinfunction "A_1") (pintype "passive"))
    )
    (net (code "45") (name "Net-(Q8-C)") (class "Default")
      (node (ref "C3") (pin "2") (pinfunction "2_2") (pintype "passive"))
      (node (ref "Q8") (pin "3") (pinfunction "C_3") (pintype "passive"))
      (node (ref "R27") (pin "2") (pinfunction "2_2") (pintype "passive"))
      (node (ref "R29") (pin "1") (pinfunction "1_1") (pintype "passive"))
      (node (ref "ZD2") (pin "1") (pinfunction "A_1") (pintype "passive"))
    )
    (net (code "46") (name "Net-(Q8-E)") (class "Default")
      (node (ref "D3") (pin "2") (pinfunction "2_2") (pintype "passive"))
      (node (ref "Q8") (pin "2") (pinfunction "E_2") (pintype "passive"))
      (node (ref "Q9") (pin "1") (pinfunction "G_1") (pintype "passive"))
      (node (ref "R29") (pin "2") (pinfunction "2_2") (pintype "passive"))
    )
    (net (code "47") (name "Net-(Q10-B)") (class "Default")
      (node (ref "Q10") (pin "1") (pinfunction "B_1") (pintype "passive"))
      (node (ref "R28") (pin "2") (pinfunction "2_2") (pintype "passive"))
    )
    (net (code "48") (name "Net-(Q10-C)") (class "Default")
      (node (ref "D3") (pin "1") (pinfunction "1_1") (pintype "passive"))
      (node (ref "Q10") (pin "3") (pinfunction "C_3") (pintype "passive"))
      (node (ref "Q8") (pin "1") (pinfunction "B_1") (pintype "passive"))
      (node (ref "R27") (pin "1") (pinfunction "1_1") (pintype "passive"))
    )
    (net (code "49") (name "Net-(Q11-B)") (class "Default")
      (node (ref "D4") (pin "1") (pinfunction "1_1") (pintype "passive"))
      (node (ref "Q11") (pin "1") (pinfunction "B_1") (pintype "passive"))
      (node (ref "Q13") (pin "3") (pinfunction "C_3") (pintype "passive"))
      (node (ref "R30") (pin "1") (pinfunction "1_1") (pintype "passive"))
    )
    (net (code "50") (name "Net-(Q11-C)") (class "Default")
      (node (ref "C11") (pin "2") (pinfunction "2_2") (pintype "passive"))
      (node (ref "Q11") (pin "3") (pinfunction "C_3") (pintype "passive"))
      (node (ref "R30") (pin "2") (pinfunction "2_2") (pintype "passive"))
      (node (ref "R32") (pin "1") (pinfunction "1_1") (pintype "passive"))
      (node (ref "ZD3") (pin "1") (pinfunction "A_1") (pintype "passive"))
    )
    (net (code "51") (name "Net-(Q11-E)") (class "Default")
      (node (ref "D4") (pin "2") (pinfunction "2_2") (pintype "passive"))
      (node (ref "Q11") (pin "2") (pinfunction "E_2") (pintype "passive"))
      (node (ref "Q12") (pin "1") (pinfunction "G_1") (pintype "passive"))
      (node (ref "R32") (pin "2") (pinfunction "2_2") (pintype "passive"))
    )
    (net (code "52") (name "Net-(Q13-B)") (class "Default")
      (node (ref "Q13") (pin "1") (pinfunction "B_1") (pintype "passive"))
      (node (ref "R31") (pin "2") (pinfunction "2_2") (pintype "passive"))
    )
    (net (code "53") (name "Net-(U1-PA11)") (class "Default")
      (node (ref "R6") (pin "1") (pinfunction "1_1") (pintype "passive"))
      (node (ref "U1") (pin "44") (pinfunction "PA11_44") (pintype "passive"))
    )
    (net (code "54") (name "Net-(U1-PA12)") (class "Default")
      (node (ref "R5") (pin "1") (pinfunction "1_1") (pintype "passive"))
      (node (ref "U1") (pin "45") (pinfunction "PA12_45") (pintype "passive"))
    )
    (net (code "55") (name "Net-(U5-BOOT)") (class "Default")
      (node (ref "C7") (pin "2") (pinfunction "2_2") (pintype "passive"))
      (node (ref "U5") (pin "2") (pinfunction "BOOT_2") (pintype "passive"))
    )
    (net (code "56") (name "Net-(U5-FB)") (class "Default")
      (node (ref "R1") (pin "2") (pinfunction "2_2") (pintype "passive"))
      (node (ref "R4") (pin "1") (pinfunction "1_1") (pintype "passive"))
      (node (ref "U5") (pin "4") (pinfunction "FB_4") (pintype "passive"))
    )
    (net (code "57") (name "Net-(U5-SW)") (class "Default")
      (node (ref "C7") (pin "1") (pinfunction "1_1") (pintype "passive"))
      (node (ref "L1") (pin "2") (pinfunction "2_2") (pintype "passive"))
      (node (ref "U5") (pin "1") (pinfunction "SW_1") (pintype "passive"))
    )
    (net (code "58") (name "Net-(U5-VCC)") (class "Default")
      (node (ref "C40") (pin "2") (pinfunction "2_2") (pintype "passive"))
      (node (ref "U5") (pin "3") (pinfunction "VCC_3") (pintype "passive"))
    )
    (net (code "59") (name "VCC") (class "Default")
      (node (ref "C17") (pin "2") (pinfunction "2_2") (pintype "passive"))
      (node (ref "C21") (pin "2") (pinfunction "2_2") (pintype "passive"))
      (node (ref "C22") (pin "2") (pinfunction "2_2") (pintype "passive"))
      (node (ref "C23") (pin "2") (pinfunction "2_2") (pintype "passive"))
      (node (ref "C24") (pin "1") (pinfunction "1_1") (pintype "passive"))
      (node (ref "C25") (pin "1") (pinfunction "1_1") (pintype "passive"))
      (node (ref "C26") (pin "1") (pinfunction "1_1") (pintype "passive"))
      (node (ref "C27") (pin "1") (pinfunction "1_1") (pintype "passive"))
      (node (ref "C4") (pin "2") (pinfunction "2_2") (pintype "passive"))
      (node (ref "C46") (pin "1") (pinfunction "1_1") (pintype "passive"))
      (node (ref "C5") (pin "1") (pinfunction "1_1") (pintype "passive"))
      (node (ref "C6") (pin "1") (pinfunction "1_1") (pintype "passive"))
      (node (ref "C8") (pin "1") (pinfunction "1_1") (pintype "passive"))
      (node (ref "Q12") (pin "3") (pinfunction "S_3") (pintype "passive"))
      (node (ref "Q6") (pin "3") (pinfunction "S_3") (pintype "passive"))
      (node (ref "Q9") (pin "3") (pinfunction "S_3") (pintype "passive"))
      (node (ref "U2") (pin "8") (pinfunction "V+_8") (pintype "passive"))
      (node (ref "U3") (pin "8") (pinfunction "V+_8") (pintype "passive"))
      (node (ref "U4") (pin "1") (pinfunction "+VS_1") (pintype "passive"))
      (node (ref "U5") (pin "5") (pinfunction "EN/SYNC_5") (pintype "passive"))
      (node (ref "U5") (pin "7") (pinfunction "VIN_7") (pintype "passive"))
      (node (ref "U7") (pin "8") (pinfunction "V+_8") (pintype "passive"))
      (node (ref "ZD1") (pin "2") (pinfunction "K_2") (pintype "passive"))
      (node (ref "ZD2") (pin "2") (pinfunction "K_2") (pintype "passive"))
      (node (ref "ZD3") (pin "2") (pinfunction "K_2") (pintype "passive"))
    )
    (net (code "60") (name "unconnected-(U1-PA2-Pad16)") (class "Default")
      (node (ref "U1") (pin "16") (pinfunction "PA2_16") (pintype "passive+no_connect"))
    )
    (net (code "61") (name "unconnected-(U1-PA3-Pad18)") (class "Default")
      (node (ref "U1") (pin "18") (pinfunction "PA3_18") (pintype "passive+no_connect"))
    )
    (net (code "62") (name "unconnected-(U1-PA15-Pad50)") (class "Default")
      (node (ref "U1") (pin "50") (pinfunction "PA15_50") (pintype "passive+no_connect"))
    )
    (net (code "63") (name "unconnected-(U1-PB0-Pad26)") (class "Default")
      (node (ref "U1") (pin "26") (pinfunction "PB0_26") (pintype "passive+no_connect"))
    )
    (net (code "64") (name "unconnected-(U1-PB1-Pad27)") (class "Default")
      (node (ref "U1") (pin "27") (pinfunction "PB1_27") (pintype "passive+no_connect"))
    )
    (net (code "65") (name "unconnected-(U1-PB3-Pad55)") (class "Default")
      (node (ref "U1") (pin "55") (pinfunction "PB3_55") (pintype "passive+no_connect"))
    )
    (net (code "66") (name "unconnected-(U1-PB4-Pad56)") (class "Default")
      (node (ref "U1") (pin "56") (pinfunction "PB4_56") (pintype "passive+no_connect"))
    )
    (net (code "67") (name "unconnected-(U1-PB5-Pad57)") (class "Default")
      (node (ref "U1") (pin "57") (pinfunction "PB5_57") (pintype "passive+no_connect"))
    )
    (net (code "68") (name "unconnected-(U1-PB6-Pad58)") (class "Default")
      (node (ref "U1") (pin "58") (pinfunction "PB6_58") (pintype "passive+no_connect"))
    )
    (net (code "69") (name "unconnected-(U1-PB7-Pad59)") (class "Default")
      (node (ref "U1") (pin "59") (pinfunction "PB7_59") (pintype "passive+no_connect"))
    )
    (net (code "70") (name "unconnected-(U1-PB15-Pad35)") (class "Default")
      (node (ref "U1") (pin "35") (pinfunction "PB15_35") (pintype "passive+no_connect"))
    )
    (net (code "71") (name "unconnected-(U1-PC0-Pad8)") (class "Default")
      (node (ref "U1") (pin "8") (pinfunction "PC0_8") (pintype "passive+no_connect"))
    )
    (net (code "72") (name "unconnected-(U1-PC1-Pad9)") (class "Default")
      (node (ref "U1") (pin "9") (pinfunction "PC1_9") (pintype "passive+no_connect"))
    )
    (net (code "73") (name "unconnected-(U1-PC4-Pad24)") (class "Default")
      (node (ref "U1") (pin "24") (pinfunction "PC4_24") (pintype "passive+no_connect"))
    )
    (net (code "74") (name "unconnected-(U1-PC5-Pad25)") (class "Default")
      (node (ref "U1") (pin "25") (pinfunction "PC5_25") (pintype "passive+no_connect"))
    )
    (net (code "75") (name "unconnected-(U1-PC6-Pad37)") (class "Default")
      (node (ref "U1") (pin "37") (pinfunction "PC6_37") (pintype "passive+no_connect"))
    )
    (net (code "76") (name "unconnected-(U1-PC7-Pad38)") (class "Default")
      (node (ref "U1") (pin "38") (pinfunction "PC7_38") (pintype "passive+no_connect"))
    )
    (net (code "77") (name "unconnected-(U1-PC8-Pad39)") (class "Default")
      (node (ref "U1") (pin "39") (pinfunction "PC8_39") (pintype "passive+no_connect"))
    )
    (net (code "78") (name "unconnected-(U1-PC9-Pad40)") (class "Default")
      (node (ref "U1") (pin "40") (pinfunction "PC9_40") (pintype "passive+no_connect"))
    )
    (net (code "79") (name "unconnected-(U1-PC10-Pad51)") (class "Default")
      (node (ref "U1") (pin "51") (pinfunction "PC10_51") (pintype "passive+no_connect"))
    )
    (net (code "80") (name "unconnected-(U1-PC11-Pad52)") (class "Default")
      (node (ref "U1") (pin "52") (pinfunction "PC11_52") (pintype "passive+no_connect"))
    )
    (net (code "81") (name "unconnected-(U1-PC12-Pad53)") (class "Default")
      (node (ref "U1") (pin "53") (pinfunction "PC12_53") (pintype "passive+no_connect"))
    )
    (net (code "82") (name "unconnected-(U1-PD2-Pad54)") (class "Default")
      (node (ref "U1") (pin "54") (pinfunction "PD2_54") (pintype "passive+no_connect"))
    )
    (net (code "83") (name "unconnected-(U1-PD8-Pad36)") (class "Default")
      (node (ref "U1") (pin "36") (pinfunction "PD8_36") (pintype "passive+no_connect"))
    )
    (net (code "84") (name "unconnected-(U1-PF6-Pad47)") (class "Default")
      (node (ref "U1") (pin "47") (pinfunction "PF6_47") (pintype "passive+no_connect"))
    )
    (net (code "85") (name "unconnected-(U1-PF7-Pad48)") (class "Default")
      (node (ref "U1") (pin "48") (pinfunction "PF7_48") (pintype "passive+no_connect"))
    )
    (net (code "86") (name "unconnected-(USBC1-PadA2)") (class "Default")
      (node (ref "USBC1") (pin "A2") (pinfunction "A2_A2") (pintype "passive+no_connect"))
    )
    (net (code "87") (name "unconnected-(USBC1-PadA3)") (class "Default")
      (node (ref "USBC1") (pin "A3") (pinfunction "A3_A3") (pintype "passive+no_connect"))
    )
    (net (code "88") (name "unconnected-(USBC1-PadA4)") (class "Default")
      (node (ref "USBC1") (pin "A4") (pinfunction "A4_A4") (pintype "passive+no_connect"))
    )
    (net (code "89") (name "unconnected-(USBC1-PadA5)") (class "Default")
      (node (ref "USBC1") (pin "A5") (pinfunction "A5_A5") (pintype "passive+no_connect"))
    )
    (net (code "90") (name "unconnected-(USBC1-PadA8)") (class "Default")
      (node (ref "USBC1") (pin "A8") (pinfunction "A8_A8") (pintype "passive+no_connect"))
    )
    (net (code "91") (name "unconnected-(USBC1-PadA9)") (class "Default")
      (node (ref "USBC1") (pin "A9") (pinfunction "A9_A9") (pintype "passive+no_connect"))
    )
    (net (code "92") (name "unconnected-(USBC1-PadA10)") (class "Default")
      (node (ref "USBC1") (pin "A10") (pinfunction "A10_A10") (pintype "passive+no_connect"))
    )
    (net (code "93") (name "unconnected-(USBC1-PadA11)") (class "Default")
      (node (ref "USBC1") (pin "A11") (pinfunction "A11_A11") (pintype "passive+no_connect"))
    )
    (net (code "94") (name "unconnected-(USBC1-PadB2)") (class "Default")
      (node (ref "USBC1") (pin "B2") (pinfunction "B2_B2") (pintype "passive+no_connect"))
    )
    (net (code "95") (name "unconnected-(USBC1-PadB3)") (class "Default")
      (node (ref "USBC1") (pin "B3") (pinfunction "B3_B3") (pintype "passive+no_connect"))
    )
    (net (code "96") (name "unconnected-(USBC1-PadB4)") (class "Default")
      (node (ref "USBC1") (pin "B4") (pinfunction "B4_B4") (pintype "passive+no_connect"))
    )
    (net (code "97") (name "unconnected-(USBC1-PadB5)") (class "Default")
      (node (ref "USBC1") (pin "B5") (pinfunction "B5_B5") (pintype "passive+no_connect"))
    )
    (net (code "98") (name "unconnected-(USBC1-PadB8)") (class "Default")
      (node (ref "USBC1") (pin "B8") (pinfunction "B8_B8") (pintype "passive+no_connect"))
    )
    (net (code "99") (name "unconnected-(USBC1-PadB9)") (class "Default")
      (node (ref "USBC1") (pin "B9") (pinfunction "B9_B9") (pintype "passive+no_connect"))
    )
    (net (code "100") (name "unconnected-(USBC1-PadB10)") (class "Default")
      (node (ref "USBC1") (pin "B10") (pinfunction "B10_B10") (pintype "passive+no_connect"))
    )
    (net (code "101") (name "unconnected-(USBC1-PadB11)") (class "Default")
      (node (ref "USBC1") (pin "B11") (pinfunction "B11_B11") (pintype "passive+no_connect"))
    )
  )
)
